# PCBStudy_LEDLight.net
KiCad netlist of a schematic drawn in Altium Designer
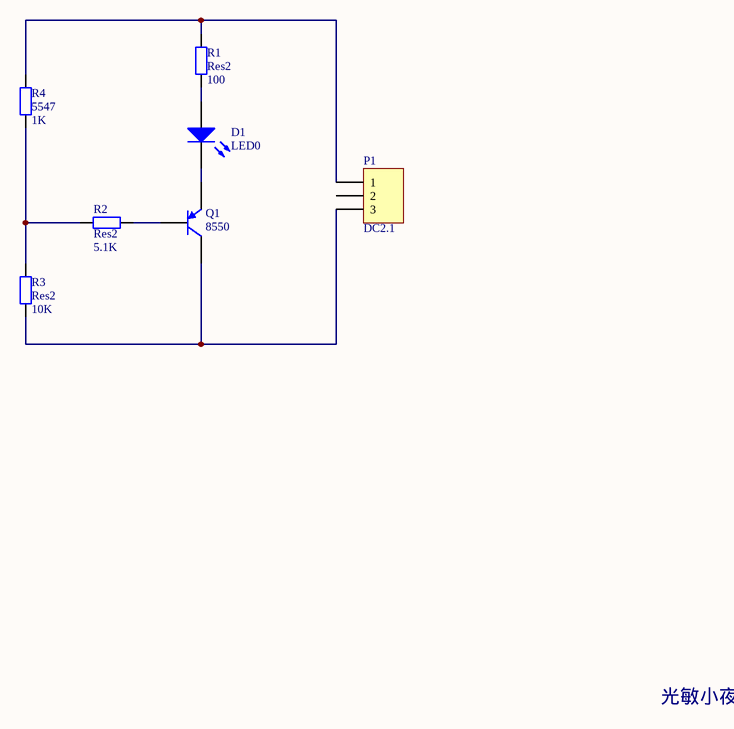
[diagram p0: PCBStudy(LEDLight).SchDoc]

(export (version "E")
  (design (tool "Eeschema 10.0.6"))
  (components
    (comp (ref "D1")
      (value "LED0")
      (footprint "PCBStudy(LEDLight):0805")
      (description "Typical INFRARED GaAs LED")
      (fields (field (name "PUBLISHER") "Altium Limited"))
      (libsource (lib "Miscellaneous Devices") (part "LED0"))
    )
    (comp (ref "P1")
      (value "DC2.1")
      (footprint "PCBStudy(LEDLight):DC2.1")
      (description "Header, 3-Pin")
      (fields (field (name "PUBLISHER") "Altium Limited"))
      (libsource (lib "Miscellaneous Connectors") (part "Header 3"))
    )
    (comp (ref "Q1")
      (value "8550")
      (footprint "PCBStudy(LEDLight):SOT-23")
      (description "PNP Bipolar Transistor")
      (fields (field (name "PUBLISHER") "Altium Limited"))
      (libsource (lib "Miscellaneous Devices") (part "PNP"))
    )
    (comp (ref "R1")
      (value "Res2")
      (footprint "PCBStudy(LEDLight):0805")
      (description "Resistor")
      (fields (field (name "ALTIUM_VALUE") "100") (field (name "PUBLISHER") "Altium Limited"))
      (libsource (lib "Miscellaneous Devices") (part "Res2"))
    )
    (comp (ref "R2")
      (value "Res2")
      (footprint "PCBStudy(LEDLight):0805")
      (description "Resistor")
      (fields (field (name "ALTIUM_VALUE") "5.1K") (field (name "PUBLISHER") "Altium Limited"))
      (libsource (lib "") (part "Res2_1"))
    )
    (comp (ref "R3")
      (value "Res2")
      (footprint "PCBStudy(LEDLight):0805")
      (description "Resistor")
      (fields (field (name "ALTIUM_VALUE") "10K") (field (name "PUBLISHER") "Altium Limited"))
      (libsource (lib "Miscellaneous Devices") (part "Res2"))
    )
    (comp (ref "R4")
      (value "5547")
      (footprint "PCBStudy(LEDLight):5547")
      (description "Resistor")
      (fields (field (name "ALTIUM_VALUE") "1K") (field (name "PUBLISHER") "Altium Limited"))
      (libsource (lib "Miscellaneous Devices") (part "Res2"))
    )
  )
  (nets
    (net (code "1") (name "Net-(D1-A)") (class "Default")
      (node (ref "D1") (pin "1") (pinfunction "A_1") (pintype "passive"))
      (node (ref "R1") (pin "1") (pinfunction "1_1") (pintype "passive"))
    )
    (net (code "2") (name "Net-(D1-K)") (class "Default")
      (node (ref "D1") (pin "2") (pinfunction "K_2") (pintype "passive"))
      (node (ref "Q1") (pin "3") (pinfunction "E_3") (pintype "passive"))
    )
    (net (code "3") (name "Net-(P1-Pad1)") (class "Default")
      (node (ref "P1") (pin "1") (pinfunction "1_1") (pintype "passive"))
      (node (ref "R1") (pin "2") (pinfunction "2_2") (pintype "passive"))
      (node (ref "R4") (pin "2") (pinfunction "2_2") (pintype "passive"))
    )
    (net (code "4") (name "Net-(Q1-B)") (class "Default")
      (node (ref "Q1") (pin "2") (pinfunction "B_2") (pintype "passive"))
      (node (ref "R2") (pin "2") (pinfunction "2_2") (pintype "passive"))
    )
    (net (code "5") (name "Net-(Q1-C)") (class "Default")
      (node (ref "P1") (pin "3") (pinfunction "3_3") (pintype "passive"))
      (node (ref "Q1") (pin "1") (pinfunction "C_1") (pintype "passive"))
      (node (ref "R3") (pin "1") (pinfunction "1_1") (pintype "passive"))
    )
    (net (code "6") (name "Net-(R2-Pad1)") (class "Default")
      (node (ref "R2") (pin "1") (pinfunction "1_1") (pintype "passive"))
      (node (ref "R3") (pin "2") (pinfunction "2_2") (pintype "passive"))
      (node (ref "R4") (pin "1") (pinfunction "1_1") (pintype "passive"))
    )
    (net (code "7") (name "unconnected-(P1-Pad2)") (class "Default")
      (node (ref "P1") (pin "2") (pinfunction "2_2") (pintype "passive"))
    )
  )
)
